# 4_periferals.net
KiCad netlist of a schematic drawn in Altium Designer
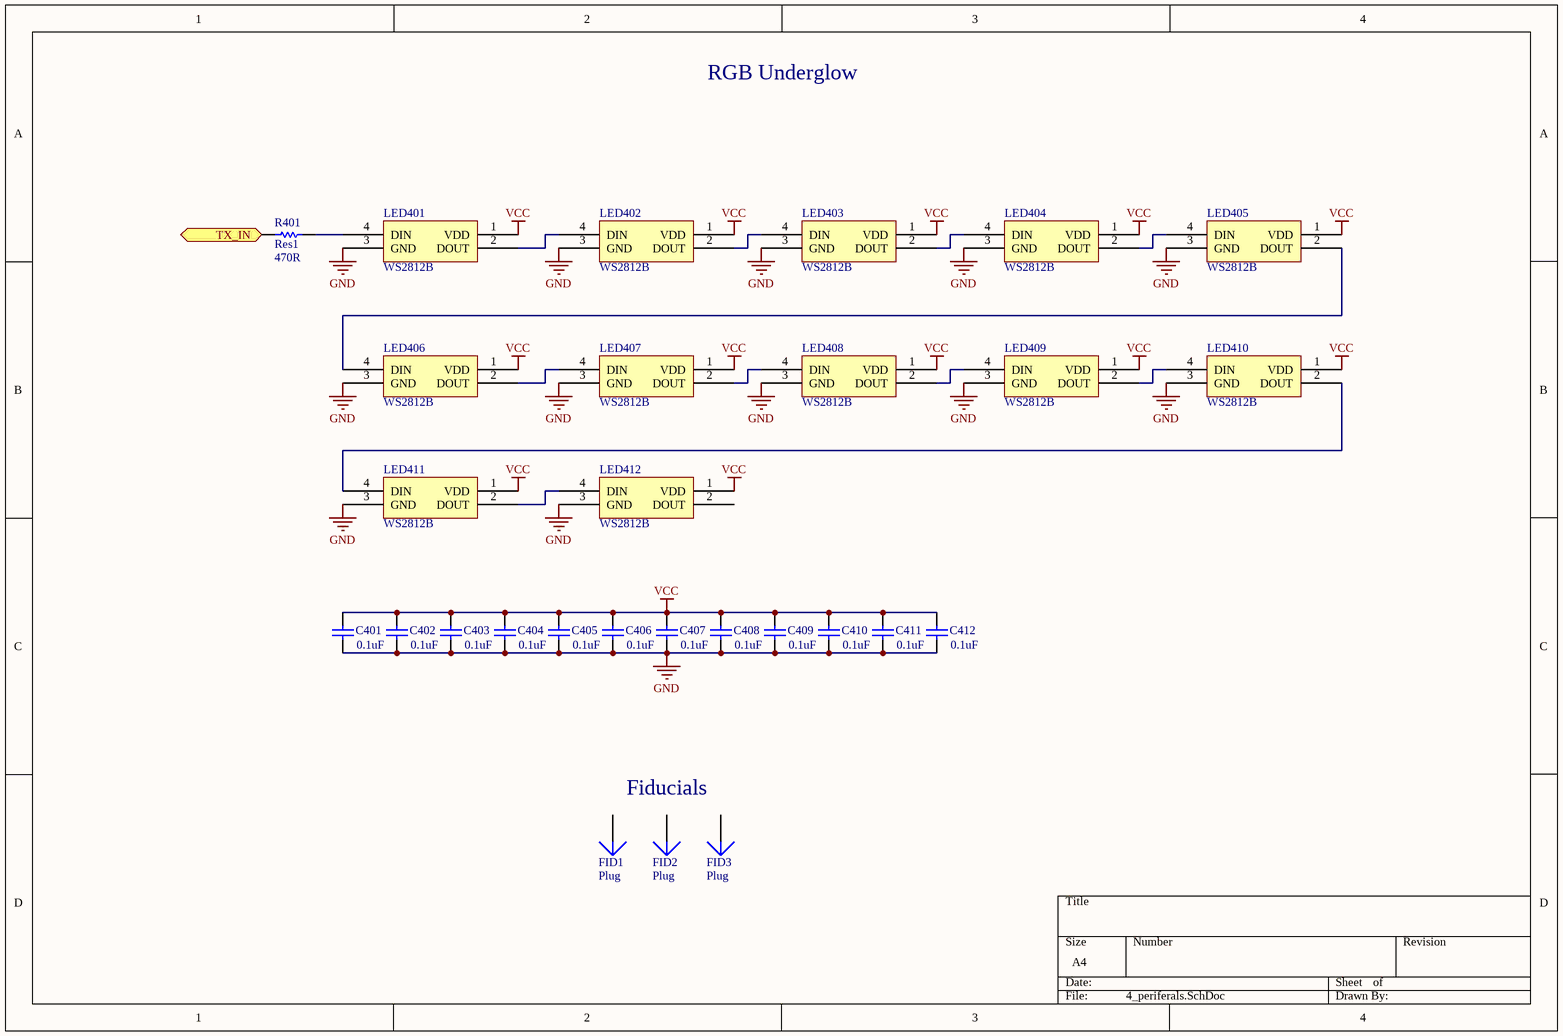
[diagram p0: 4_periferals.SchDoc]

(export (version "E")
  (design (tool "Eeschema 10.0.6"))
  (components
    (comp (ref "C401")
      (value "0.1uF")
      (footprint "C0603[1608]")
      (description "Capacitor")
      (fields (field (name "MFG") "KEMET") (field (name "MRF.PART") "CC0603KRX7R9BB104"))
      (libsource (lib "Miscellaneous Devices") (part "Cap"))
    )
    (comp (ref "C402")
      (value "0.1uF")
      (footprint "C0603[1608]")
      (description "Capacitor")
      (fields (field (name "MFG") "KEMET") (field (name "MRF.PART") "CC0603KRX7R9BB104"))
      (libsource (lib "Miscellaneous Devices") (part "Cap"))
    )
    (comp (ref "C403")
      (value "0.1uF")
      (footprint "C0603[1608]")
      (description "Capacitor")
      (fields (field (name "MFG") "KEMET") (field (name "MRF.PART") "CC0603KRX7R9BB104"))
      (libsource (lib "Miscellaneous Devices") (part "Cap"))
    )
    (comp (ref "C404")
      (value "0.1uF")
      (footprint "C0603[1608]")
      (description "Capacitor")
      (fields (field (name "MFG") "KEMET") (field (name "MRF.PART") "CC0603KRX7R9BB104"))
      (libsource (lib "Miscellaneous Devices") (part "Cap"))
    )
    (comp (ref "C405")
      (value "0.1uF")
      (footprint "C0603[1608]")
      (description "Capacitor")
      (fields (field (name "MFG") "KEMET") (field (name "MRF.PART") "CC0603KRX7R9BB104"))
      (libsource (lib "Miscellaneous Devices") (part "Cap"))
    )
    (comp (ref "C406")
      (value "0.1uF")
      (footprint "C0603[1608]")
      (description "Capacitor")
      (fields (field (name "MFG") "KEMET") (field (name "MRF.PART") "CC0603KRX7R9BB104"))
      (libsource (lib "Miscellaneous Devices") (part "Cap"))
    )
    (comp (ref "C407")
      (value "0.1uF")
      (footprint "C0603[1608]")
      (description "Capacitor")
      (fields (field (name "MFG") "KEMET") (field (name "MRF.PART") "CC0603KRX7R9BB104"))
      (libsource (lib "Miscellaneous Devices") (part "Cap"))
    )
    (comp (ref "C408")
      (value "0.1uF")
      (footprint "C0603[1608]")
      (description "Capacitor")
      (fields (field (name "MFG") "KEMET") (field (name "MRF.PART") "CC0603KRX7R9BB104"))
      (libsource (lib "Miscellaneous Devices") (part "Cap"))
    )
    (comp (ref "C409")
      (value "0.1uF")
      (footprint "C0603[1608]")
      (description "Capacitor")
      (fields (field (name "MFG") "KEMET") (field (name "MRF.PART") "CC0603KRX7R9BB104"))
      (libsource (lib "Miscellaneous Devices") (part "Cap"))
    )
    (comp (ref "C410")
      (value "0.1uF")
      (footprint "C0603[1608]")
      (description "Capacitor")
      (fields (field (name "MFG") "KEMET") (field (name "MRF.PART") "CC0603KRX7R9BB104"))
      (libsource (lib "Miscellaneous Devices") (part "Cap"))
    )
    (comp (ref "C411")
      (value "0.1uF")
      (footprint "C0603[1608]")
      (description "Capacitor")
      (fields (field (name "MFG") "KEMET") (field (name "MRF.PART") "CC0603KRX7R9BB104"))
      (libsource (lib "Miscellaneous Devices") (part "Cap"))
    )
    (comp (ref "C412")
      (value "0.1uF")
      (footprint "C0603[1608]")
      (description "Capacitor")
      (fields (field (name "MFG") "KEMET") (field (name "MRF.PART") "CC0603KRX7R9BB104"))
      (libsource (lib "Miscellaneous Devices") (part "Cap"))
    )
    (comp (ref "FID1")
      (value "Plug")
      (footprint "Fiducial_Nordic")
      (libsource (lib "Miscellaneous Connectors") (part "Plug"))
    )
    (comp (ref "FID2")
      (value "Plug")
      (footprint "Fiducial_Nordic")
      (libsource (lib "Miscellaneous Connectors") (part "Plug"))
    )
    (comp (ref "FID3")
      (value "Plug")
      (footprint "Fiducial_Nordic")
      (libsource (lib "Miscellaneous Connectors") (part "Plug"))
    )
    (comp (ref "LED401") (value "WS2812B") (footprint "WS2812B") (libsource (lib "Keebs") (part "WS2812B")))
    (comp (ref "LED402") (value "WS2812B") (footprint "WS2812B") (libsource (lib "Keebs") (part "WS2812B")))
    (comp (ref "LED403") (value "WS2812B") (footprint "WS2812B") (libsource (lib "Keebs") (part "WS2812B")))
    (comp (ref "LED404") (value "WS2812B") (footprint "WS2812B") (libsource (lib "Keebs") (part "WS2812B")))
    (comp (ref "LED405") (value "WS2812B") (footprint "WS2812B") (libsource (lib "Keebs") (part "WS2812B")))
    (comp (ref "LED406") (value "WS2812B") (footprint "WS2812B") (libsource (lib "Keebs") (part "WS2812B")))
    (comp (ref "LED407") (value "WS2812B") (footprint "WS2812B") (libsource (lib "Keebs") (part "WS2812B")))
    (comp (ref "LED408") (value "WS2812B") (footprint "WS2812B") (libsource (lib "Keebs") (part "WS2812B")))
    (comp (ref "LED409") (value "WS2812B") (footprint "WS2812B") (libsource (lib "Keebs") (part "WS2812B")))
    (comp (ref "LED410") (value "WS2812B") (footprint "WS2812B") (libsource (lib "Keebs") (part "WS2812B")))
    (comp (ref "LED411") (value "WS2812B") (footprint "WS2812B") (libsource (lib "Keebs") (part "WS2812B")))
    (comp (ref "LED412") (value "WS2812B") (footprint "WS2812B") (libsource (lib "Keebs") (part "WS2812B")))
    (comp (ref "R401")
      (value "Res1")
      (footprint "R0603[1608]")
      (description "Resistor")
      (fields
        (field (name "ALTIUM_VALUE") "470R")
        (field (name "MFG") "Panasonic Electronic Components")
        (field (name "MRF.PART") "0603WAF4700T5E")
      )
      (libsource (lib "Miscellaneous Devices") (part "Res1"))
    )
  )
  (nets
    (net (code "1") (name "/TX_IN") (class "Default")
      (node (ref "R401") (pin "1") (pinfunction "1_1") (pintype "passive"))
    )
    (net (code "2") (name "GND") (class "Default")
      (node (ref "C401") (pin "1") (pinfunction "1_1") (pintype "passive"))
      (node (ref "C402") (pin "1") (pinfunction "1_1") (pintype "passive"))
      (node (ref "C403") (pin "1") (pinfunction "1_1") (pintype "passive"))
      (node (ref "C404") (pin "1") (pinfunction "1_1") (pintype "passive"))
      (node (ref "C405") (pin "1") (pinfunction "1_1") (pintype "passive"))
      (node (ref "C406") (pin "1") (pinfunction "1_1") (pintype "passive"))
      (node (ref "C407") (pin "1") (pinfunction "1_1") (pintype "passive"))
      (node (ref "C408") (pin "1") (pinfunction "1_1") (pintype "passive"))
      (node (ref "C409") (pin "1") (pinfunction "1_1") (pintype "passive"))
      (node (ref "C410") (pin "1") (pinfunction "1_1") (pintype "passive"))
      (node (ref "C411") (pin "1") (pinfunction "1_1") (pintype "passive"))
      (node (ref "C412") (pin "1") (pinfunction "1_1") (pintype "passive"))
      (node (ref "LED401") (pin "3") (pinfunction "GND_3") (pintype "passive"))
      (node (ref "LED402") (pin "3") (pinfunction "GND_3") (pintype "passive"))
      (node (ref "LED403") (pin "3") (pinfunction "GND_3") (pintype "passive"))
      (node (ref "LED404") (pin "3") (pinfunction "GND_3") (pintype "passive"))
      (node (ref "LED405") (pin "3") (pinfunction "GND_3") (pintype "passive"))
      (node (ref "LED406") (pin "3") (pinfunction "GND_3") (pintype "passive"))
      (node (ref "LED407") (pin "3") (pinfunction "GND_3") (pintype "passive"))
      (node (ref "LED408") (pin "3") (pinfunction "GND_3") (pintype "passive"))
      (node (ref "LED409") (pin "3") (pinfunction "GND_3") (pintype "passive"))
      (node (ref "LED410") (pin "3") (pinfunction "GND_3") (pintype "passive"))
      (node (ref "LED411") (pin "3") (pinfunction "GND_3") (pintype "passive"))
      (node (ref "LED412") (pin "3") (pinfunction "GND_3") (pintype "passive"))
    )
    (net (code "3") (name "Net-(LED401-DIN)") (class "Default")
      (node (ref "LED401") (pin "4") (pinfunction "DIN_4") (pintype "passive"))
      (node (ref "R401") (pin "2") (pinfunction "2_2") (pintype "passive"))
    )
    (net (code "4") (name "Net-(LED401-DOUT)") (class "Default")
      (node (ref "LED401") (pin "2") (pinfunction "DOUT_2") (pintype "passive"))
      (node (ref "LED402") (pin "4") (pinfunction "DIN_4") (pintype "passive"))
    )
    (net (code "5") (name "Net-(LED402-DOUT)") (class "Default")
      (node (ref "LED402") (pin "2") (pinfunction "DOUT_2") (pintype "passive"))
      (node (ref "LED403") (pin "4") (pinfunction "DIN_4") (pintype "passive"))
    )
    (net (code "6") (name "Net-(LED403-DOUT)") (class "Default")
      (node (ref "LED403") (pin "2") (pinfunction "DOUT_2") (pintype "passive"))
      (node (ref "LED404") (pin "4") (pinfunction "DIN_4") (pintype "passive"))
    )
    (net (code "7") (name "Net-(LED404-DOUT)") (class "Default")
      (node (ref "LED404") (pin "2") (pinfunction "DOUT_2") (pintype "passive"))
      (node (ref "LED405") (pin "4") (pinfunction "DIN_4") (pintype "passive"))
    )
    (net (code "8") (name "Net-(LED405-DOUT)") (class "Default")
      (node (ref "LED405") (pin "2") (pinfunction "DOUT_2") (pintype "passive"))
      (node (ref "LED406") (pin "4") (pinfunction "DIN_4") (pintype "passive"))
    )
    (net (code "9") (name "Net-(LED406-DOUT)") (class "Default")
      (node (ref "LED406") (pin "2") (pinfunction "DOUT_2") (pintype "passive"))
      (node (ref "LED407") (pin "4") (pinfunction "DIN_4") (pintype "passive"))
    )
    (net (code "10") (name "Net-(LED407-DOUT)") (class "Default")
      (node (ref "LED407") (pin "2") (pinfunction "DOUT_2") (pintype "passive"))
      (node (ref "LED408") (pin "4") (pinfunction "DIN_4") (pintype "passive"))
    )
    (net (code "11") (name "Net-(LED408-DOUT)") (class "Default")
      (node (ref "LED408") (pin "2") (pinfunction "DOUT_2") (pintype "passive"))
      (node (ref "LED409") (pin "4") (pinfunction "DIN_4") (pintype "passive"))
    )
    (net (code "12") (name "Net-(LED409-DOUT)") (class "Default")
      (node (ref "LED409") (pin "2") (pinfunction "DOUT_2") (pintype "passive"))
      (node (ref "LED410") (pin "4") (pinfunction "DIN_4") (pintype "passive"))
    )
    (net (code "13") (name "Net-(LED410-DOUT)") (class "Default")
      (node (ref "LED410") (pin "2") (pinfunction "DOUT_2") (pintype "passive"))
      (node (ref "LED411") (pin "4") (pinfunction "DIN_4") (pintype "passive"))
    )
    (net (code "14") (name "Net-(LED411-DOUT)") (class "Default")
      (node (ref "LED411") (pin "2") (pinfunction "DOUT_2") (pintype "passive"))
      (node (ref "LED412") (pin "4") (pinfunction "DIN_4") (pintype "passive"))
    )
    (net (code "15") (name "VCC") (class "Default")
      (node (ref "C401") (pin "2") (pinfunction "2_2") (pintype "passive"))
      (node (ref "C402") (pin "2") (pinfunction "2_2") (pintype "passive"))
      (node (ref "C403") (pin "2") (pinfunction "2_2") (pintype "passive"))
      (node (ref "C404") (pin "2") (pinfunction "2_2") (pintype "passive"))
      (node (ref "C405") (pin "2") (pinfunction "2_2") (pintype "passive"))
      (node (ref "C406") (pin "2") (pinfunction "2_2") (pintype "passive"))
      (node (ref "C407") (pin "2") (pinfunction "2_2") (pintype "passive"))
      (node (ref "C408") (pin "2") (pinfunction "2_2") (pintype "passive"))
      (node (ref "C409") (pin "2") (pinfunction "2_2") (pintype "passive"))
      (node (ref "C410") (pin "2") (pinfunction "2_2") (pintype "passive"))
      (node (ref "C411") (pin "2") (pinfunction "2_2") (pintype "passive"))
      (node (ref "C412") (pin "2") (pinfunction "2_2") (pintype "passive"))
      (node (ref "LED401") (pin "1") (pinfunction "VDD_1") (pintype "passive"))
      (node (ref "LED402") (pin "1") (pinfunction "VDD_1") (pintype "passive"))
      (node (ref "LED403") (pin "1") (pinfunction "VDD_1") (pintype "passive"))
      (node (ref "LED404") (pin "1") (pinfunction "VDD_1") (pintype "passive"))
      (node (ref "LED405") (pin "1") (pinfunction "VDD_1") (pintype "passive"))
      (node (ref "LED406") (pin "1") (pinfunction "VDD_1") (pintype "passive"))
      (node (ref "LED407") (pin "1") (pinfunction "VDD_1") (pintype "passive"))
      (node (ref "LED408") (pin "1") (pinfunction "VDD_1") (pintype "passive"))
      (node (ref "LED409") (pin "1") (pinfunction "VDD_1") (pintype "passive"))
      (node (ref "LED410") (pin "1") (pinfunction "VDD_1") (pintype "passive"))
      (node (ref "LED411") (pin "1") (pinfunction "VDD_1") (pintype "passive"))
      (node (ref "LED412") (pin "1") (pinfunction "VDD_1") (pintype "passive"))
    )
    (net (code "16") (name "unconnected-(FID1-Pad1)") (class "Default")
      (node (ref "FID1") (pin "1") (pinfunction "1_1") (pintype "passive"))
    )
    (net (code "17") (name "unconnected-(FID2-Pad1)") (class "Default")
      (node (ref "FID2") (pin "1") (pinfunction "1_1") (pintype "passive"))
    )
    (net (code "18") (name "unconnected-(FID3-Pad1)") (class "Default")
      (node (ref "FID3") (pin "1") (pinfunction "1_1") (pintype "passive"))
    )
    (net (code "19") (name "unconnected-(LED412-DOUT-Pad2)") (class "Default")
      (node (ref "LED412") (pin "2") (pinfunction "DOUT_2") (pintype "passive"))
    )
  )
)
